# ref_board.net
KiCad netlist of a schematic drawn in EAGLE
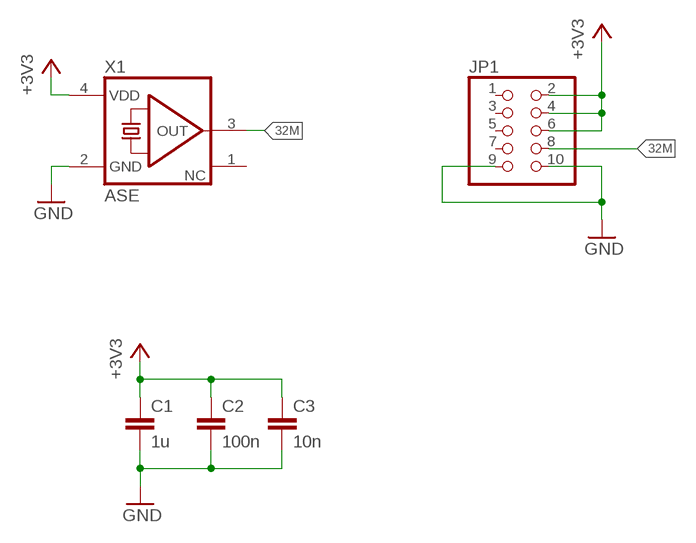
[diagram p0: schematic, sheet 1]

(export (version "E")
  (design (tool "Eeschema 10.0.6"))
  (components
    (comp (ref "C1")
      (value "1u")
      (footprint "eagle-import:C1206")
      (libsource (lib "eagle-import") (part "C-EUC1206"))
    )
    (comp (ref "C2")
      (value "100n")
      (footprint "eagle-import:C0805")
      (libsource (lib "eagle-import") (part "C-EUC0805"))
    )
    (comp (ref "C3")
      (value "10n")
      (footprint "eagle-import:C0805")
      (libsource (lib "eagle-import") (part "C-EUC0805"))
    )
    (comp (ref "JP1")
      (value "PINHD-2X5/90")
      (footprint "eagle-import:2X05_90")
      (libsource (lib "eagle-import") (part "PINHD-2X5/90"))
    )
    (comp (ref "X1")
      (value "ASE")
      (footprint "eagle-import:ASE")
      (libsource (lib "eagle-import") (part "ASE"))
    )
  )
  (nets
    (net (code "1") (name "+3V3") (class "Default")
      (node (ref "C1") (pin "1") (pinfunction "1_1") (pintype "passive"))
      (node (ref "C2") (pin "1") (pinfunction "1_1") (pintype "passive"))
      (node (ref "C3") (pin "1") (pinfunction "1_1") (pintype "passive"))
      (node (ref "JP1") (pin "2") (pinfunction "2_2") (pintype "passive"))
      (node (ref "JP1") (pin "4") (pinfunction "4_4") (pintype "passive"))
      (node (ref "JP1") (pin "6") (pinfunction "6_6") (pintype "passive"))
      (node (ref "X1") (pin "4") (pinfunction "VDD_4") (pintype "power_in"))
    )
    (net (code "2") (name "32M") (class "Default")
      (node (ref "JP1") (pin "8") (pinfunction "8_8") (pintype "passive"))
      (node (ref "X1") (pin "3") (pinfunction "OUT_3") (pintype "output"))
    )
    (net (code "3") (name "GND") (class "Default")
      (node (ref "C1") (pin "2") (pinfunction "2_2") (pintype "passive"))
      (node (ref "C2") (pin "2") (pinfunction "2_2") (pintype "passive"))
      (node (ref "C3") (pin "2") (pinfunction "2_2") (pintype "passive"))
      (node (ref "JP1") (pin "10") (pinfunction "10_10") (pintype "passive"))
      (node (ref "JP1") (pin "9") (pinfunction "9_9") (pintype "passive"))
      (node (ref "X1") (pin "2") (pinfunction "GND_2") (pintype "power_in"))
    )
    (net (code "4") (name "unconnected-(JP1-Pad1)") (class "Default")
      (node (ref "JP1") (pin "1") (pinfunction "1_1") (pintype "passive"))
    )
    (net (code "5") (name "unconnected-(JP1-Pad3)") (class "Default")
      (node (ref "JP1") (pin "3") (pinfunction "3_3") (pintype "passive"))
    )
    (net (code "6") (name "unconnected-(JP1-Pad5)") (class "Default")
      (node (ref "JP1") (pin "5") (pinfunction "5_5") (pintype "passive"))
    )
    (net (code "7") (name "unconnected-(JP1-Pad7)") (class "Default")
      (node (ref "JP1") (pin "7") (pinfunction "7_7") (pintype "passive"))
    )
    (net (code "8") (name "unconnected-(X1-NC-Pad1)") (class "Default")
      (node (ref "X1") (pin "1") (pinfunction "NC_1") (pintype "input"))
    )
  )
)
